# BMP280.net
KiCad netlist of a schematic drawn in Altium Designer
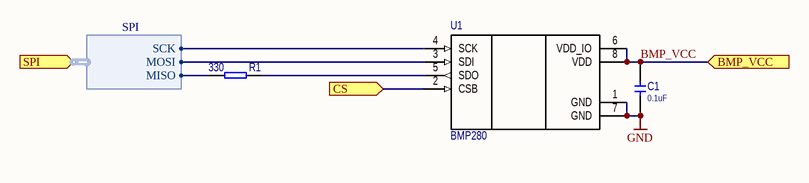
[diagram p0: BMP280.SchDoc]

(export (version "E")
  (design (tool "Eeschema 10.0.6"))
  (components
    (comp (ref "C1")
      (value "0.1uF")
      (footprint "CERCAP 0402")
      (description "Capacitor")
      (fields (field (name "Comment") "CERCAP 0402 0.1uF * X7R"))
      (libsource (lib "!main") (part "!Capacitor"))
    )
    (comp (ref "R1")
      (value "330")
      (footprint "RES 0402")
      (description "Resistor")
      (fields (field (name "Comment") "RES 0402 330"))
      (libsource (lib "!main") (part "!Resistor"))
    )
    (comp (ref "U1")
      (value "BMP280")
      (footprint "LGA8_BMP280")
      (description "Temp/Pres/Hum")
      (libsource (lib "sensors") (part "BMP(E)280"))
    )
  )
  (nets
    (net (code "2") (name "/BMP_VCC") (class "Default")
      (node (ref "C1") (pin "2") (pintype "passive"))
      (node (ref "U1") (pin "6") (pinfunction "VDD_IO_6") (pintype "power_in"))
      (node (ref "U1") (pin "8") (pinfunction "VDD_8") (pintype "power_in"))
    )
    (net (code "3") (name "/CS") (class "Default")
      (node (ref "U1") (pin "2") (pinfunction "CSB_2") (pintype "input"))
    )
    (net (code "4") (name "/MISO") (class "Default")
      (node (ref "R1") (pin "1") (pinfunction "11_1") (pintype "passive"))
    )
    (net (code "5") (name "/MOSI") (class "Default")
      (node (ref "U1") (pin "3") (pinfunction "SDI_3") (pintype "input"))
    )
    (net (code "6") (name "/SCK") (class "Default")
      (node (ref "U1") (pin "4") (pinfunction "SCK_4") (pintype "input"))
    )
    (net (code "8") (name "GND") (class "Default")
      (node (ref "C1") (pin "1") (pintype "passive"))
      (node (ref "U1") (pin "1") (pinfunction "GND_1") (pintype "power_in"))
      (node (ref "U1") (pin "7") (pinfunction "GND_7") (pintype "power_in"))
    )
    (net (code "9") (name "Net-(R1-12)") (class "Default")
      (node (ref "R1") (pin "2") (pinfunction "12_2") (pintype "passive"))
      (node (ref "U1") (pin "5") (pinfunction "SDO_5") (pintype "output"))
    )
  )
)
